# schematics_v10.net
KiCad netlist of a schematic drawn in EAGLE
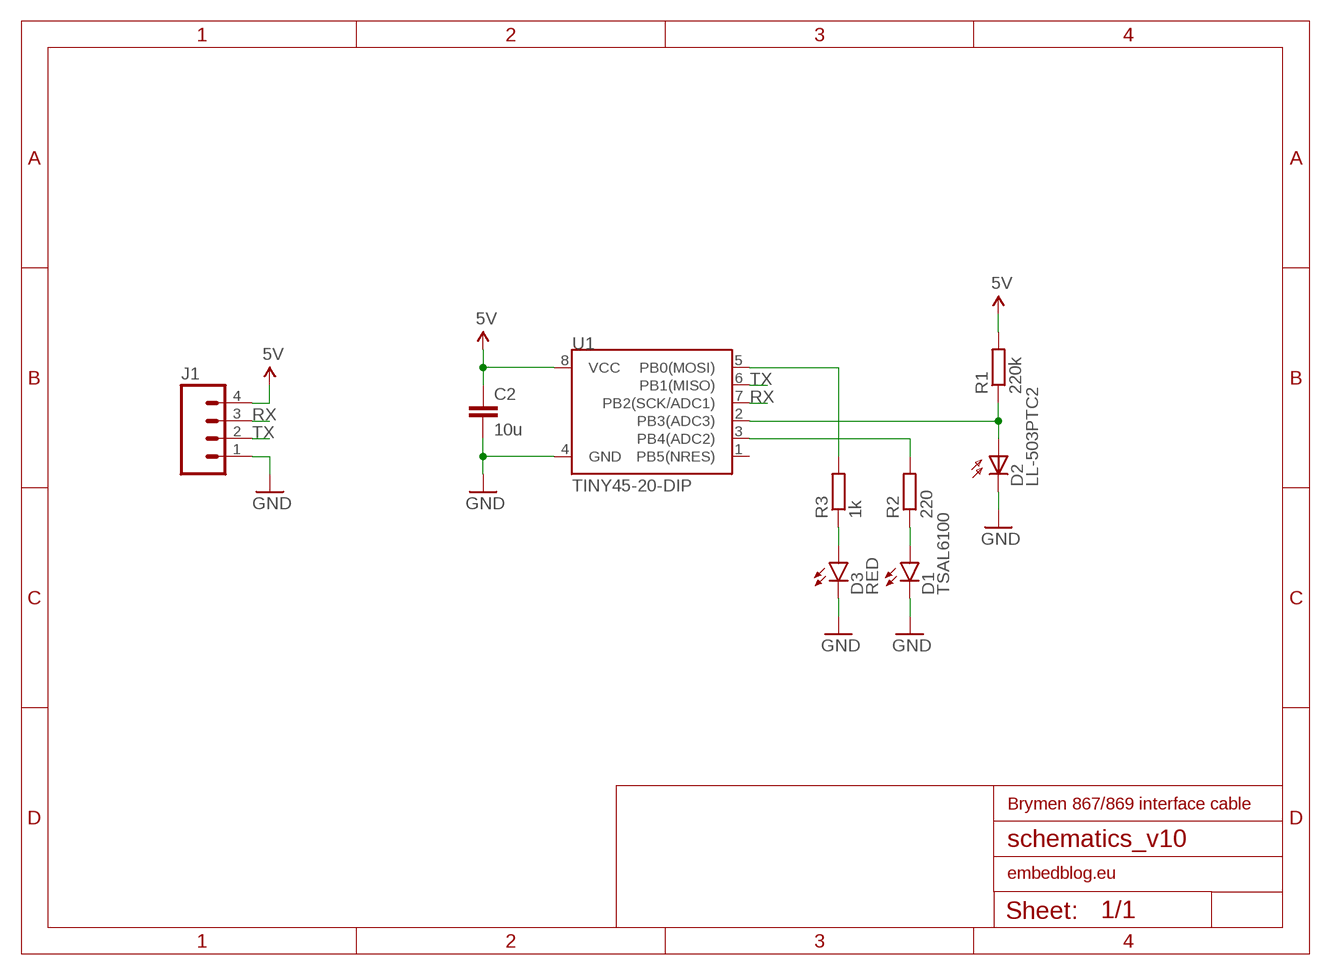
[diagram p0: schematic, sheet 1]

(export (version "E")
  (design (tool "Eeschema 10.0.6"))
  (components
    (comp (ref "C2")
      (value "10u")
      (footprint "eagle-import:C0805")
      (libsource (lib "eagle-import") (part "C-EUC0805"))
    )
    (comp (ref "D1")
      (value "TSAL6100")
      (footprint "eagle-import:LED5MM")
      (libsource (lib "eagle-import") (part "LED5MM"))
    )
    (comp (ref "D2")
      (value "LL-503PTC2")
      (footprint "eagle-import:BPX65")
      (fields (field (name "MPN") "BPX65."))
      (libsource (lib "eagle-import") (part "BPX65"))
    )
    (comp (ref "D3")
      (value "RED")
      (footprint "eagle-import:LED5MM")
      (libsource (lib "eagle-import") (part "LED5MM"))
    )
    (comp (ref "J1")
      (value "M04PTH")
      (footprint "eagle-import:1X04")
      (libsource (lib "eagle-import") (part "M04PTH"))
    )
    (comp (ref "R1")
      (value "220k")
      (footprint "eagle-import:R3216")
      (libsource (lib "eagle-import") (part "R-EU_R3216"))
    )
    (comp (ref "R2")
      (value "220")
      (footprint "eagle-import:R3216")
      (libsource (lib "eagle-import") (part "R-EU_R3216"))
    )
    (comp (ref "R3")
      (value "1k")
      (footprint "eagle-import:R3216")
      (libsource (lib "eagle-import") (part "R-EU_R3216"))
    )
    (comp (ref "U1")
      (value "TINY45-20-DIP")
      (footprint "eagle-import:DIP08")
      (libsource (lib "eagle-import") (part "ATTINY45TINY45-20-DIP"))
    )
  )
  (nets
    (net (code "1") (name "/RX") (class "Default")
      (node (ref "J1") (pin "3") (pinfunction "3_3") (pintype "passive"))
      (node (ref "U1") (pin "7") (pinfunction "PB2(SCK/ADC1)_7") (pintype "bidirectional"))
    )
    (net (code "2") (name "/TX") (class "Default")
      (node (ref "J1") (pin "2") (pinfunction "2_2") (pintype "passive"))
      (node (ref "U1") (pin "6") (pinfunction "PB1(MISO)_6") (pintype "bidirectional"))
    )
    (net (code "3") (name "5V") (class "Default")
      (node (ref "C2") (pin "1") (pinfunction "1_1") (pintype "passive"))
      (node (ref "J1") (pin "4") (pinfunction "4_4") (pintype "passive"))
      (node (ref "R1") (pin "2") (pinfunction "2_2") (pintype "passive"))
      (node (ref "U1") (pin "8") (pinfunction "VCC_8") (pintype "bidirectional"))
    )
    (net (code "4") (name "GND") (class "Default")
      (node (ref "C2") (pin "2") (pinfunction "2_2") (pintype "passive"))
      (node (ref "D1") (pin "K") (pinfunction "C_K") (pintype "passive"))
      (node (ref "D2") (pin "K") (pinfunction "C_K") (pintype "passive"))
      (node (ref "D3") (pin "K") (pinfunction "C_K") (pintype "passive"))
      (node (ref "J1") (pin "1") (pinfunction "1_1") (pintype "passive"))
      (node (ref "U1") (pin "4") (pinfunction "GND_4") (pintype "bidirectional"))
    )
    (net (code "5") (name "Net-(D1-PadA)") (class "Default")
      (node (ref "D1") (pin "A") (pinfunction "A_A") (pintype "passive"))
      (node (ref "R2") (pin "1") (pinfunction "1_1") (pintype "passive"))
    )
    (net (code "6") (name "Net-(D3-PadA)") (class "Default")
      (node (ref "D3") (pin "A") (pinfunction "A_A") (pintype "passive"))
      (node (ref "R3") (pin "1") (pinfunction "1_1") (pintype "passive"))
    )
    (net (code "7") (name "Net-(U1-PB0(MOSI))") (class "Default")
      (node (ref "R3") (pin "2") (pinfunction "2_2") (pintype "passive"))
      (node (ref "U1") (pin "5") (pinfunction "PB0(MOSI)_5") (pintype "bidirectional"))
    )
    (net (code "8") (name "Net-(U1-PB3(ADC3))") (class "Default")
      (node (ref "D2") (pin "A") (pinfunction "A_A") (pintype "passive"))
      (node (ref "R1") (pin "1") (pinfunction "1_1") (pintype "passive"))
      (node (ref "U1") (pin "2") (pinfunction "PB3(ADC3)_2") (pintype "bidirectional"))
    )
    (net (code "9") (name "Net-(U1-PB4(ADC2))") (class "Default")
      (node (ref "R2") (pin "2") (pinfunction "2_2") (pintype "passive"))
      (node (ref "U1") (pin "3") (pinfunction "PB4(ADC2)_3") (pintype "bidirectional"))
    )
    (net (code "10") (name "unconnected-(U1-PB5(NRES)-Pad1)") (class "Default")
      (node (ref "U1") (pin "1") (pinfunction "PB5(NRES)_1") (pintype "bidirectional"))
    )
  )
)
